# BlinkyBoard_NickBluhm_RevA.net
KiCad netlist of a schematic drawn in EAGLE
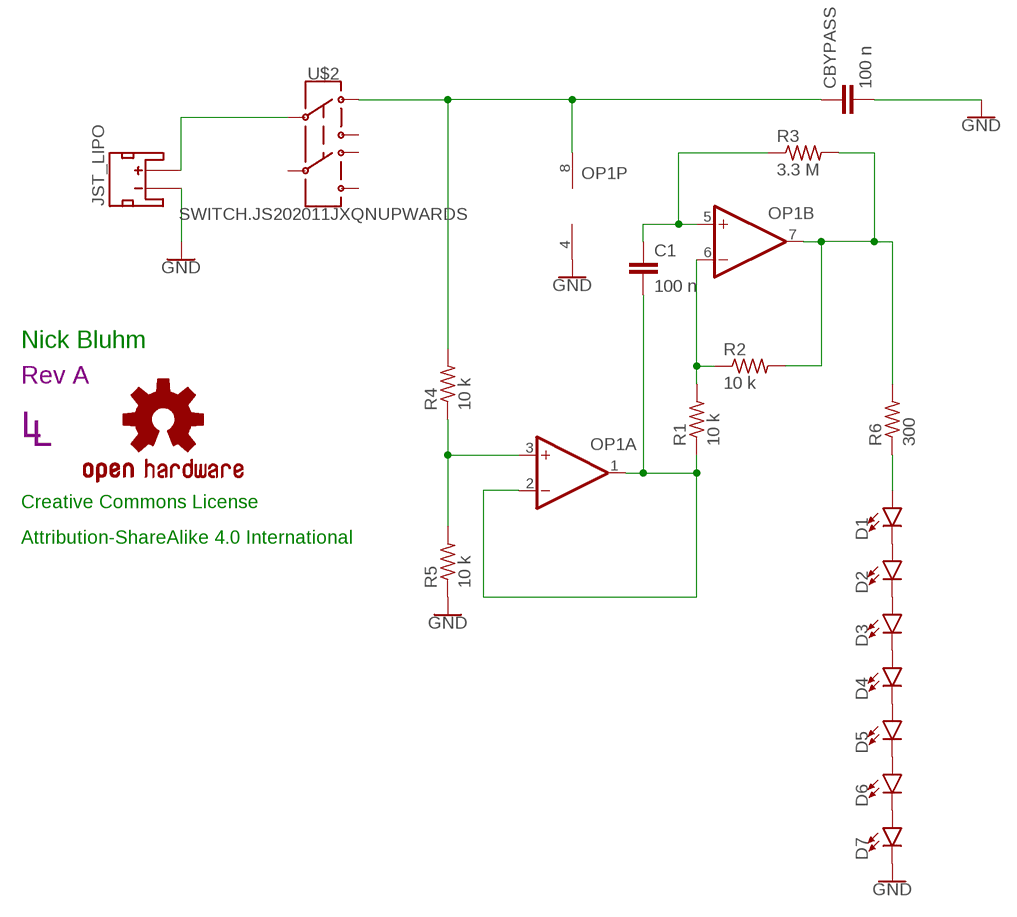
[diagram p0: schematic, sheet 1]

(export (version "E")
  (design (tool "Eeschema 10.0.6"))
  (components
    (comp (ref "C1")
      (value "100 n")
      (footprint "eagle-import:C0402")
      (libsource (lib "eagle-import") (part "CAPACITOR0402"))
    )
    (comp (ref "CBYPASS")
      (value "100 n")
      (footprint "eagle-import:C0402")
      (libsource (lib "eagle-import") (part "CAPACITOR0402"))
    )
    (comp (ref "D1")
      (value "LED0603")
      (footprint "eagle-import:LED-0603")
      (libsource (lib "eagle-import") (part "LED0603"))
    )
    (comp (ref "D2")
      (value "LED0603")
      (footprint "eagle-import:LED-0603")
      (libsource (lib "eagle-import") (part "LED0603"))
    )
    (comp (ref "D3")
      (value "LED0603")
      (footprint "eagle-import:LED-0603")
      (libsource (lib "eagle-import") (part "LED0603"))
    )
    (comp (ref "D4")
      (value "LED0603")
      (footprint "eagle-import:LED-0603")
      (libsource (lib "eagle-import") (part "LED0603"))
    )
    (comp (ref "D5")
      (value "LED0603")
      (footprint "eagle-import:LED-0603")
      (libsource (lib "eagle-import") (part "LED0603"))
    )
    (comp (ref "D6")
      (value "LED0603")
      (footprint "eagle-import:LED-0603")
      (libsource (lib "eagle-import") (part "LED0603"))
    )
    (comp (ref "D7")
      (value "LED0603")
      (footprint "eagle-import:LED-0603")
      (libsource (lib "eagle-import") (part "LED0603"))
    )
    (comp (ref "JST_LIPO")
      (value "3.7 V")
      (footprint "eagle-import:JST-2-SMD")
      (libsource (lib "eagle-import") (part "JST_2MM_MALE"))
    )
    (comp (ref "LOGO1")
      (value "OSHW-LOGOL-COPPER")
      (footprint "eagle-import:OSHW-LOGO-L_COPPER")
      (libsource (lib "eagle-import") (part "OSHW-LOGOL-COPPER"))
    )
    (comp (ref "OP1")
      (value "OP-DUALRM")
      (footprint "eagle-import:MSOP08")
      (fields (field (name "MF") "ALTERA CORPORATION") (field (name "MPN") "AD8607ARMZ-REEL"))
      (libsource (lib "eagle-import") (part "OP-DUALRM"))
    )
    (comp (ref "R1")
      (value "10 k")
      (footprint "eagle-import:R0402")
      (libsource (lib "eagle-import") (part "RESISTOR0402"))
    )
    (comp (ref "R2")
      (value "10 k")
      (footprint "eagle-import:R0402")
      (libsource (lib "eagle-import") (part "RESISTOR0402"))
    )
    (comp (ref "R3")
      (value "3.3 M")
      (footprint "eagle-import:R0402")
      (libsource (lib "eagle-import") (part "RESISTOR0402"))
    )
    (comp (ref "R4")
      (value "10 k")
      (footprint "eagle-import:R0402")
      (libsource (lib "eagle-import") (part "RESISTOR0402"))
    )
    (comp (ref "R5")
      (value "10 k")
      (footprint "eagle-import:R0402")
      (libsource (lib "eagle-import") (part "RESISTOR0402"))
    )
    (comp (ref "R6")
      (value "300")
      (footprint "eagle-import:R0402")
      (libsource (lib "eagle-import") (part "RESISTOR0402"))
    )
    (comp (ref "U$2")
      (value "SWITCH.JS202011JXQNUPWARDS")
      (footprint "eagle-import:SWITCH.00")
      (libsource (lib "eagle-import") (part "SWITCH.JS202011JXQNUPWARDS"))
    )
    (comp (ref "U$4")
      (value "REVISION.A")
      (footprint "eagle-import:REV.A")
      (libsource (lib "eagle-import") (part "REVISION.A"))
    )
    (comp (ref "U$5")
      (value "LINNES.LAB.LOGO")
      (footprint "eagle-import:LINNES.LAB.LOGO")
      (libsource (lib "eagle-import") (part "LINNES.LAB.LOGO"))
    )
  )
  (nets
    (net (code "1") (name "GND") (class "Default")
      (node (ref "CBYPASS") (pin "2") (pinfunction "2_2") (pintype "passive"))
      (node (ref "D7") (pin "C") (pinfunction "C_C") (pintype "passive"))
      (node (ref "JST_LIPO") (pin "1") (pinfunction "-_1") (pintype "bidirectional"))
      (node (ref "OP1") (pin "4") (pinfunction "V-_4") (pintype "power_in"))
      (node (ref "R5") (pin "1") (pinfunction "1_1") (pintype "passive"))
    )
    (net (code "2") (name "Net-(D1-PadA)") (class "Default")
      (node (ref "D1") (pin "A") (pinfunction "A_A") (pintype "passive"))
      (node (ref "R6") (pin "1") (pinfunction "1_1") (pintype "passive"))
    )
    (net (code "3") (name "Net-(D1-PadC)") (class "Default")
      (node (ref "D1") (pin "C") (pinfunction "C_C") (pintype "passive"))
      (node (ref "D2") (pin "A") (pinfunction "A_A") (pintype "passive"))
    )
    (net (code "4") (name "Net-(D2-PadC)") (class "Default")
      (node (ref "D2") (pin "C") (pinfunction "C_C") (pintype "passive"))
      (node (ref "D3") (pin "A") (pinfunction "A_A") (pintype "passive"))
    )
    (net (code "5") (name "Net-(D3-PadC)") (class "Default")
      (node (ref "D3") (pin "C") (pinfunction "C_C") (pintype "passive"))
      (node (ref "D4") (pin "A") (pinfunction "A_A") (pintype "passive"))
    )
    (net (code "6") (name "Net-(D4-PadC)") (class "Default")
      (node (ref "D4") (pin "C") (pinfunction "C_C") (pintype "passive"))
      (node (ref "D5") (pin "A") (pinfunction "A_A") (pintype "passive"))
    )
    (net (code "7") (name "Net-(D5-PadC)") (class "Default")
      (node (ref "D5") (pin "C") (pinfunction "C_C") (pintype "passive"))
      (node (ref "D6") (pin "A") (pinfunction "A_A") (pintype "passive"))
    )
    (net (code "8") (name "Net-(D6-PadC)") (class "Default")
      (node (ref "D6") (pin "C") (pinfunction "C_C") (pintype "passive"))
      (node (ref "D7") (pin "A") (pinfunction "A_A") (pintype "passive"))
    )
    (net (code "9") (name "Net-(JST_LIPO-+)") (class "Default")
      (node (ref "JST_LIPO") (pin "2") (pinfunction "+_2") (pintype "bidirectional"))
      (node (ref "U$2") (pin "2") (pinfunction "2_2") (pintype "bidirectional"))
    )
    (net (code "10") (name "Net-(OP1A-+IN)") (class "Default")
      (node (ref "OP1") (pin "3") (pinfunction "+IN_3") (pintype "input"))
      (node (ref "R4") (pin "1") (pinfunction "1_1") (pintype "passive"))
      (node (ref "R5") (pin "2") (pinfunction "2_2") (pintype "passive"))
    )
    (net (code "11") (name "Net-(OP1A--IN)") (class "Default")
      (node (ref "C1") (pin "2") (pinfunction "2_2") (pintype "passive"))
      (node (ref "OP1") (pin "1") (pinfunction "OUT_1") (pintype "output"))
      (node (ref "OP1") (pin "2") (pinfunction "-IN_2") (pintype "input"))
      (node (ref "R1") (pin "1") (pinfunction "1_1") (pintype "passive"))
    )
    (net (code "12") (name "Net-(OP1B-+IN)") (class "Default")
      (node (ref "C1") (pin "1") (pinfunction "1_1") (pintype "passive"))
      (node (ref "OP1") (pin "5") (pinfunction "+IN_5") (pintype "input"))
      (node (ref "R3") (pin "1") (pinfunction "1_1") (pintype "passive"))
    )
    (net (code "13") (name "Net-(OP1B--IN)") (class "Default")
      (node (ref "OP1") (pin "6") (pinfunction "-IN_6") (pintype "input"))
      (node (ref "R1") (pin "2") (pinfunction "2_2") (pintype "passive"))
      (node (ref "R2") (pin "1") (pinfunction "1_1") (pintype "passive"))
    )
    (net (code "14") (name "Net-(OP1B-OUT)") (class "Default")
      (node (ref "OP1") (pin "7") (pinfunction "OUT_7") (pintype "output"))
      (node (ref "R2") (pin "2") (pinfunction "2_2") (pintype "passive"))
      (node (ref "R3") (pin "2") (pinfunction "2_2") (pintype "passive"))
      (node (ref "R6") (pin "2") (pinfunction "2_2") (pintype "passive"))
    )
    (net (code "15") (name "Net-(OP1C-V+)") (class "Default")
      (node (ref "CBYPASS") (pin "1") (pinfunction "1_1") (pintype "passive"))
      (node (ref "OP1") (pin "8") (pinfunction "V+_8") (pintype "power_in"))
      (node (ref "R4") (pin "2") (pinfunction "2_2") (pintype "passive"))
      (node (ref "U$2") (pin "1") (pinfunction "1_1") (pintype "bidirectional"))
    )
    (net (code "16") (name "unconnected-(JST_LIPO-PAD1-PadNC1)") (class "Default")
      (node (ref "JST_LIPO") (pin "NC1") (pinfunction "PAD1_NC1") (pintype "bidirectional"))
    )
    (net (code "17") (name "unconnected-(JST_LIPO-PAD2-PadNC2)") (class "Default")
      (node (ref "JST_LIPO") (pin "NC2") (pinfunction "PAD2_NC2") (pintype "bidirectional"))
    )
    (net (code "18") (name "unconnected-(U$2-Pad3)") (class "Default")
      (node (ref "U$2") (pin "3") (pinfunction "3_3") (pintype "bidirectional"))
    )
    (net (code "19") (name "unconnected-(U$2-Pad5)") (class "Default")
      (node (ref "U$2") (pin "5") (pinfunction "5_5") (pintype "bidirectional"))
    )
    (net (code "20") (name "unconnected-(U$2-Pad6)") (class "Default")
      (node (ref "U$2") (pin "6") (pinfunction "6_6") (pintype "bidirectional"))
    )
    (net (code "21") (name "unconnected-(U$2-Pad7)") (class "Default")
      (node (ref "U$2") (pin "7") (pinfunction "7_7") (pintype "bidirectional"))
    )
  )
)
